# Low_Noise_PS_Filter_Only.net
KiCad netlist of a schematic drawn in EAGLE
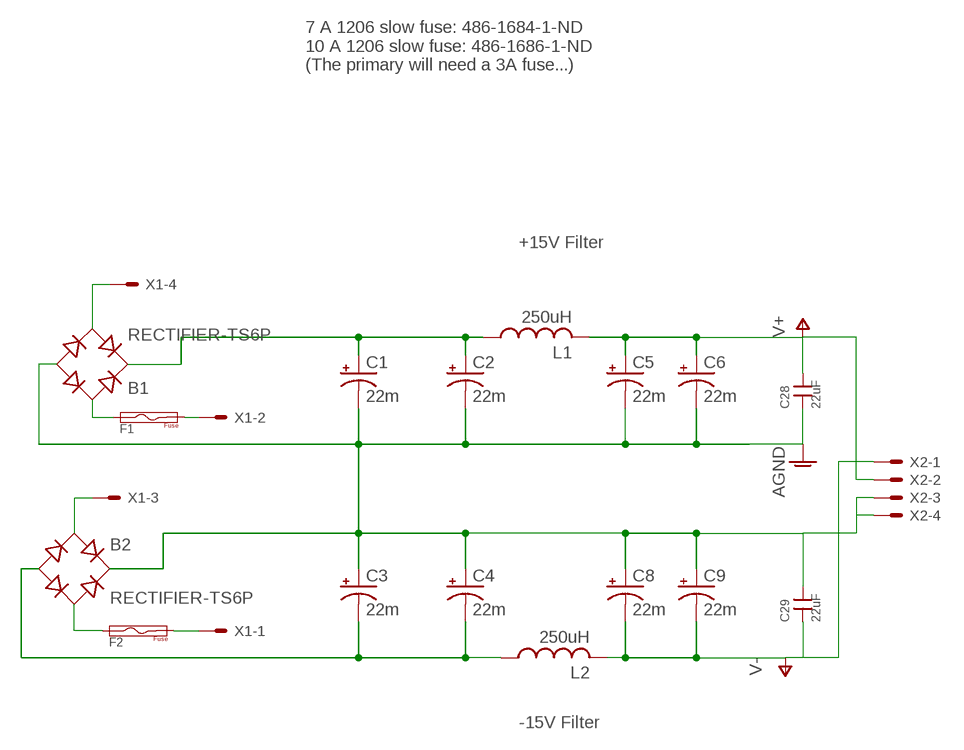
[diagram p0: schematic, sheet 1]

(export (version "E")
  (design (tool "Eeschema 10.0.6"))
  (components
    (comp (ref "B1")
      (value "RECTIFIER-TS6P")
      (footprint "eagle-import:TS6P")
      (libsource (lib "eagle-import") (part "RECTIFIER-TS6P"))
    )
    (comp (ref "B2")
      (value "RECTIFIER-TS6P")
      (footprint "eagle-import:TS6P")
      (libsource (lib "eagle-import") (part "RECTIFIER-TS6P"))
    )
    (comp (ref "C1")
      (value "22m")
      (footprint "eagle-import:EB35D")
      (libsource (lib "eagle-import") (part "CPOL-USEB35D"))
    )
    (comp (ref "C2")
      (value "22m")
      (footprint "eagle-import:EB35D")
      (libsource (lib "eagle-import") (part "CPOL-USEB35D"))
    )
    (comp (ref "C3")
      (value "22m")
      (footprint "eagle-import:EB35D")
      (libsource (lib "eagle-import") (part "CPOL-USEB35D"))
    )
    (comp (ref "C4")
      (value "22m")
      (footprint "eagle-import:EB35D")
      (libsource (lib "eagle-import") (part "CPOL-USEB35D"))
    )
    (comp (ref "C5")
      (value "22m")
      (footprint "eagle-import:EB35D")
      (libsource (lib "eagle-import") (part "CPOL-USEB35D"))
    )
    (comp (ref "C6")
      (value "22m")
      (footprint "eagle-import:EB35D")
      (libsource (lib "eagle-import") (part "CPOL-USEB35D"))
    )
    (comp (ref "C8")
      (value "22m")
      (footprint "eagle-import:EB35D")
      (libsource (lib "eagle-import") (part "CPOL-USEB35D"))
    )
    (comp (ref "C9")
      (value "22m")
      (footprint "eagle-import:EB35D")
      (libsource (lib "eagle-import") (part "CPOL-USEB35D"))
    )
    (comp (ref "C28")
      (value "22uF")
      (footprint "eagle-import:1206")
      (libsource (lib "eagle-import") (part "CAP1206"))
    )
    (comp (ref "C29")
      (value "22uF")
      (footprint "eagle-import:1206")
      (libsource (lib "eagle-import") (part "CAP1206"))
    )
    (comp (ref "F1")
      (value "FUSE1206")
      (footprint "eagle-import:FUSE1206")
      (libsource (lib "eagle-import") (part "FUSE1206"))
    )
    (comp (ref "F2")
      (value "FUSE1206")
      (footprint "eagle-import:FUSE1206")
      (libsource (lib "eagle-import") (part "FUSE1206"))
    )
    (comp (ref "L1")
      (value "250uH")
      (footprint "eagle-import:5721-RC")
      (libsource (lib "eagle-import") (part "INDUCTOR5721-RC"))
    )
    (comp (ref "L2")
      (value "250uH")
      (footprint "eagle-import:5721-RC")
      (libsource (lib "eagle-import") (part "INDUCTOR5721-RC"))
    )
    (comp (ref "X1")
      (value "5566-4")
      (footprint "eagle-import:5566-4")
      (libsource (lib "eagle-import") (part "5566-4"))
    )
    (comp (ref "X2")
      (value "5566-4")
      (footprint "eagle-import:5566-4")
      (libsource (lib "eagle-import") (part "5566-4"))
    )
  )
  (nets
    (net (code "1") (name "AGND") (class "Default")
      (node (ref "B1") (pin "-") (pinfunction "-_-") (pintype "passive"))
      (node (ref "B2") (pin "+") (pinfunction "+_+") (pintype "passive"))
      (node (ref "C1") (pin "-") (pinfunction "-_-") (pintype "passive"))
      (node (ref "C2") (pin "-") (pinfunction "-_-") (pintype "passive"))
      (node (ref "C28") (pin "1") (pinfunction "P$1_1") (pintype "passive"))
      (node (ref "C29") (pin "2") (pinfunction "P$2_2") (pintype "passive"))
      (node (ref "C3") (pin "+") (pinfunction "+_+") (pintype "passive"))
      (node (ref "C4") (pin "+") (pinfunction "+_+") (pintype "passive"))
      (node (ref "C5") (pin "-") (pinfunction "-_-") (pintype "passive"))
      (node (ref "C6") (pin "-") (pinfunction "-_-") (pintype "passive"))
      (node (ref "C8") (pin "+") (pinfunction "+_+") (pintype "passive"))
      (node (ref "C9") (pin "+") (pinfunction "+_+") (pintype "passive"))
      (node (ref "X2") (pin "3") (pinfunction "S_3") (pintype "passive"))
      (node (ref "X2") (pin "4") (pinfunction "S_4") (pintype "passive"))
    )
    (net (code "2") (name "Net-(F1-P$1)") (class "Default")
      (node (ref "B1") (pin "AC1") (pinfunction "AC1_AC1") (pintype "passive"))
      (node (ref "F1") (pin "1") (pinfunction "P$1_1") (pintype "bidirectional"))
    )
    (net (code "3") (name "Net-(F1-P$2)") (class "Default")
      (node (ref "F1") (pin "2") (pinfunction "P$2_2") (pintype "bidirectional"))
      (node (ref "X1") (pin "2") (pinfunction "S_2") (pintype "passive"))
    )
    (net (code "4") (name "Net-(F2-P$1)") (class "Default")
      (node (ref "B2") (pin "AC2") (pinfunction "AC2_AC2") (pintype "passive"))
      (node (ref "F2") (pin "1") (pinfunction "P$1_1") (pintype "bidirectional"))
    )
    (net (code "5") (name "Net-(F2-P$2)") (class "Default")
      (node (ref "F2") (pin "2") (pinfunction "P$2_2") (pintype "bidirectional"))
      (node (ref "X1") (pin "1") (pinfunction "S_1") (pintype "passive"))
    )
    (net (code "6") (name "Net-(L1-1)") (class "Default")
      (node (ref "B1") (pin "+") (pinfunction "+_+") (pintype "passive"))
      (node (ref "C1") (pin "+") (pinfunction "+_+") (pintype "passive"))
      (node (ref "C2") (pin "+") (pinfunction "+_+") (pintype "passive"))
      (node (ref "L1") (pin "P$1") (pinfunction "1_P$1") (pintype "passive"))
    )
    (net (code "7") (name "Net-(L2-1)") (class "Default")
      (node (ref "B2") (pin "-") (pinfunction "-_-") (pintype "passive"))
      (node (ref "C3") (pin "-") (pinfunction "-_-") (pintype "passive"))
      (node (ref "C4") (pin "-") (pinfunction "-_-") (pintype "passive"))
      (node (ref "L2") (pin "P$1") (pinfunction "1_P$1") (pintype "passive"))
    )
    (net (code "8") (name "Net-(X1C-S)") (class "Default")
      (node (ref "B2") (pin "AC1") (pinfunction "AC1_AC1") (pintype "passive"))
      (node (ref "X1") (pin "3") (pinfunction "S_3") (pintype "passive"))
    )
    (net (code "9") (name "Net-(X1D-S)") (class "Default")
      (node (ref "B1") (pin "AC2") (pinfunction "AC2_AC2") (pintype "passive"))
      (node (ref "X1") (pin "4") (pinfunction "S_4") (pintype "passive"))
    )
    (net (code "10") (name "V+") (class "Default")
      (node (ref "C28") (pin "2") (pinfunction "P$2_2") (pintype "passive"))
      (node (ref "C5") (pin "+") (pinfunction "+_+") (pintype "passive"))
      (node (ref "C6") (pin "+") (pinfunction "+_+") (pintype "passive"))
      (node (ref "L1") (pin "P$2") (pinfunction "2_P$2") (pintype "passive"))
      (node (ref "X2") (pin "2") (pinfunction "S_2") (pintype "passive"))
    )
    (net (code "11") (name "V-") (class "Default")
      (node (ref "C29") (pin "1") (pinfunction "P$1_1") (pintype "passive"))
      (node (ref "C8") (pin "-") (pinfunction "-_-") (pintype "passive"))
      (node (ref "C9") (pin "-") (pinfunction "-_-") (pintype "passive"))
      (node (ref "L2") (pin "P$2") (pinfunction "2_P$2") (pintype "passive"))
      (node (ref "X2") (pin "1") (pinfunction "S_1") (pintype "passive"))
    )
  )
)
